# Auto.net
KiCad netlist of a schematic drawn in Altium Designer
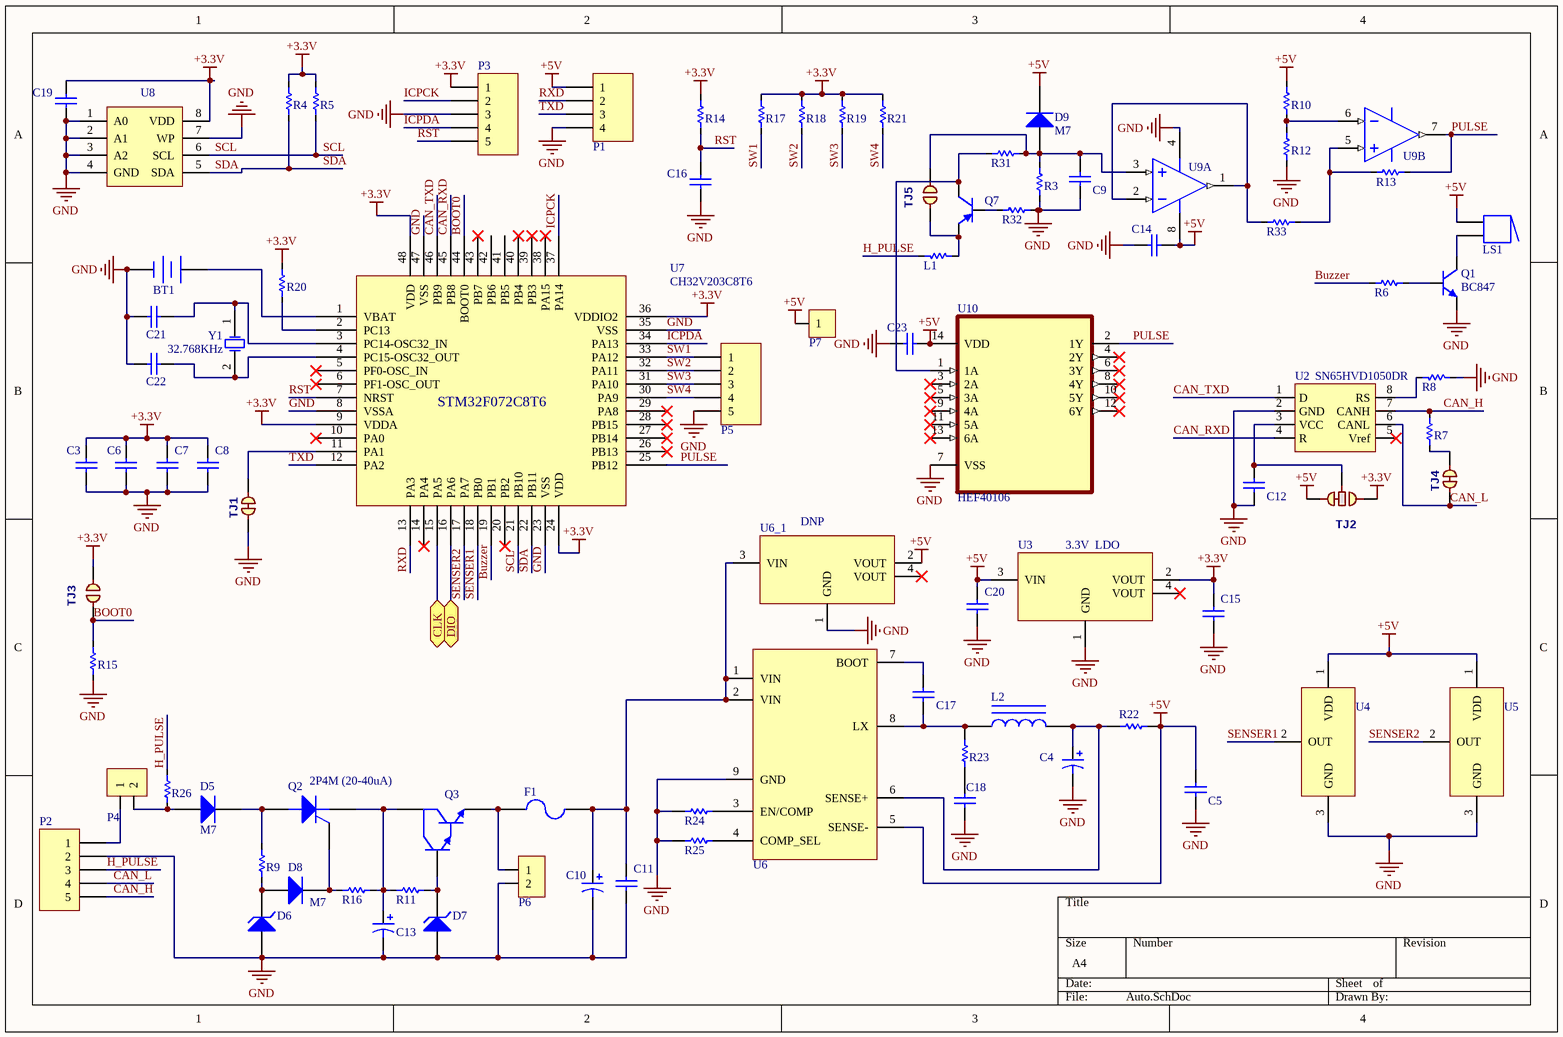
[diagram p0: Auto.SchDoc]

(export (version "E")
  (design (tool "Eeschema 10.0.6"))
  (components
    (comp (ref "BT1")
      (value "3V")
      (footprint "Battery Holder(CR2032)")
      (description "Cell Battery")
      (fields (field (name "MANUFACTURER PART NUMBER") "Standard"))
      (libsource (lib "Ravi") (part "Battery"))
    )
    (comp (ref "C3")
      (value "0.1uF/50V")
      (footprint "C0603")
      (description "CAP CER 0.1UF 50V X7R 0603")
      (fields (field (name "MANUFACTURER PART NUMBER") "0603B104K500CT"))
      (libsource (lib "Devices") (part "Capacitor_Ceramic"))
    )
    (comp (ref "C4")
      (value "220uF/16V")
      (footprint "C220uF25V")
      (description "220 µF 16 V Aluminum Electrolytic Capacitors Radial")
      (fields (field (name "MANUFACTURER PART NUMBER") "Standard"))
      (libsource (lib "Ravi") (part "Capacitor_Electrolytic"))
    )
    (comp (ref "C5")
      (value "0.1uF/50V")
      (footprint "C0603")
      (description "CAP CER 0.1UF 50V X7R 0603")
      (fields (field (name "MANUFACTURER PART NUMBER") "0603B104K500CT"))
      (libsource (lib "Ravi") (part "Capacitor_Ceramic"))
    )
    (comp (ref "C6")
      (value "0.1uF/50V")
      (footprint "C0603")
      (description "CAP CER 0.1UF 50V X7R 0603")
      (fields (field (name "MANUFACTURER PART NUMBER") "0603B104K500CT"))
      (libsource (lib "Devices") (part "Capacitor_Ceramic"))
    )
    (comp (ref "C7")
      (value "0.1uF/50V")
      (footprint "C0603")
      (description "CAP CER 0.1UF 50V X7R 0603")
      (fields (field (name "MANUFACTURER PART NUMBER") "0603B104K500CT"))
      (libsource (lib "Devices") (part "Capacitor_Ceramic"))
    )
    (comp (ref "C8")
      (value "0.1uF/50V")
      (footprint "C0603")
      (description "CAP CER 0.1UF 50V X7R 0603")
      (fields (field (name "MANUFACTURER PART NUMBER") "0603B104K500CT"))
      (libsource (lib "Devices") (part "Capacitor_Ceramic"))
    )
    (comp (ref "C9")
      (value "0.1uF/50V")
      (footprint "C0603")
      (description "CAP CER 0.1UF 50V X7R 0603")
      (fields (field (name "MANUFACTURER PART NUMBER") "0603B104K500CT"))
      (libsource (lib "Ravi") (part "Capacitor_Ceramic"))
    )
    (comp (ref "C10")
      (value "1000uF/25V")
      (footprint "C1000uF25V")
      (description "CAP ALUM 1000UF 20% 25V RADIAL")
      (fields (field (name "MANUFACTURER PART NUMBER") "Standard"))
      (libsource (lib "Ravi") (part "Capacitor_Electrolytic"))
    )
    (comp (ref "C11")
      (value "0.1uF/50V")
      (footprint "C0805")
      (description "CAP CER 0.1UF 50V X7R 0603")
      (fields (field (name "MANUFACTURER PART NUMBER") "0603B104K500CT"))
      (libsource (lib "Devices") (part "Capacitor_Ceramic"))
    )
    (comp (ref "C12")
      (value "0.1uF/50V")
      (footprint "C0603")
      (description "CAP CER 0.1UF 50V X7R 0603")
      (fields (field (name "MANUFACTURER PART NUMBER") "0603B104K500CT"))
      (libsource (lib "Devices") (part "Capacitor_Ceramic"))
    )
    (comp (ref "C13")
      (value "1000uF/50V")
      (footprint "C1000uF50V")
      (description "CAP ALUM 1000UF 20% 35V RADIAL")
      (fields (field (name "MANUFACTURER PART NUMBER") "Standard"))
      (libsource (lib "Ravi") (part "Capacitor_Electrolytic"))
    )
    (comp (ref "C14")
      (value "0.1uF/50V")
      (footprint "C0603")
      (description "CAP CER 0.1UF 50V X7R 0603")
      (fields (field (name "MANUFACTURER PART NUMBER") "0603B104K500CT"))
      (libsource (lib "Ravi") (part "Capacitor_Ceramic"))
    )
    (comp (ref "C15")
      (value "10uF")
      (footprint "C0603")
      (description "CAP CER 10UF 10V X5R 0603")
      (fields (field (name "MANUFACTURER PART NUMBER") "CL10A106MP8NNNC"))
      (libsource (lib "Devices") (part "Capacitor_Ceramic"))
    )
    (comp (ref "C16")
      (value "DNP")
      (footprint "C0603")
      (libsource (lib "Devices") (part "Capacitor_Ceramic"))
    )
    (comp (ref "C17")
      (value "0.1uF/50V")
      (footprint "C0603")
      (description "CAP CER 0.1UF 50V X7R 0603")
      (fields (field (name "MANUFACTURER PART NUMBER") "0603B104K500CT"))
      (libsource (lib "Ravi") (part "Capacitor_Ceramic"))
    )
    (comp (ref "C18")
      (value "3.3nF")
      (footprint "C0603")
      (description "CAP CER 3300PF 50V X7R 0603")
      (fields (field (name "MANUFACTURER PART NUMBER") "CC0603KRX7R9BB332"))
      (libsource (lib "Ravi") (part "Capacitor_Ceramic"))
    )
    (comp (ref "C19")
      (value "0.1uF/50V")
      (footprint "C0603")
      (description "CAP CER 0.1UF 50V X7R 0603")
      (fields (field (name "MANUFACTURER PART NUMBER") "0603B104K500CT"))
      (libsource (lib "Devices") (part "Capacitor_Ceramic"))
    )
    (comp (ref "C20")
      (value "10uF")
      (footprint "C0603")
      (description "CAP CER 10UF 10V X5R 0603")
      (fields (field (name "MANUFACTURER PART NUMBER") "CL10A106MP8NNNC"))
      (libsource (lib "Devices") (part "Capacitor_Ceramic"))
    )
    (comp (ref "C21")
      (value "22pF/50V")
      (footprint "C0603")
      (description "CAP CER 22PF 50V C0G/NPO 0603")
      (fields (field (name "MANUFACTURER PART NUMBER") "CC0603JRNPO9BN220"))
      (libsource (lib "Devices") (part "Capacitor_Ceramic"))
    )
    (comp (ref "C22")
      (value "22pF/50V")
      (footprint "C0603")
      (description "CAP CER 22PF 50V C0G/NPO 0603")
      (fields (field (name "MANUFACTURER PART NUMBER") "CC0603JRNPO9BN220"))
      (libsource (lib "Devices") (part "Capacitor_Ceramic"))
    )
    (comp (ref "C23")
      (value "0.1uF/50V")
      (footprint "C0603")
      (description "CAP CER 0.1UF 50V X7R 0603")
      (fields (field (name "MANUFACTURER PART NUMBER") "0603B104K500CT"))
      (libsource (lib "Ravi") (part "Capacitor_Ceramic"))
    )
    (comp (ref "D5")
      (value "M7")
      (footprint "DO-241")
      (description "General Purpose Diode")
      (libsource (lib "Ravi") (part "Diode"))
    )
    (comp (ref "D6")
      (value "12V/1W")
      (footprint "LL-41")
      (description "Zener Diode")
      (fields (field (name "MANUFACTURER PART NUMBER") "SML4742A-E3/61"))
      (libsource (lib "Ravi") (part "D Zener"))
    )
    (comp (ref "D7")
      (value "12V/1W")
      (footprint "LL-41")
      (description "Zener Diode")
      (fields (field (name "MANUFACTURER PART NUMBER") "SML4742A-E3/61"))
      (libsource (lib "Ravi") (part "D Zener"))
    )
    (comp (ref "D8")
      (value "M7")
      (footprint "DO-241")
      (description "General Purpose Diode")
      (libsource (lib "Ravi") (part "Diode"))
    )
    (comp (ref "D9")
      (value "M7")
      (footprint "SMA")
      (description "General Purpose Diode")
      (libsource (lib "Ravi") (part "Diode"))
    )
    (comp (ref "F1")
      (value "750mA PTC")
      (footprint "1812(PTC Fuse)")
      (description "PTC RESET FUSE 24V 750MA 1812")
      (fields (field (name "MANUFACTURER PART NUMBER") "WT-1812-075"))
      (libsource (lib "Devices") (part "Fuse"))
    )
    (comp (ref "L1")
      (value "Ferrite Bead")
      (footprint "R0603")
      (description "Ferrite Bead  200mΩ ±25% 60Ω@100MHz")
      (fields (field (name "MANUFACTURER PART NUMBER") "FCM1608KF-600T07"))
      (libsource (lib "Devices") (part "Res1"))
    )
    (comp (ref "L2")
      (value "22uH/1.8A")
      (footprint "Ferrite_Coil_22uH")
      (description "FIXED IND 22UH 1.8A 116MOHM SMD")
      (fields (field (name "MANUFACTURER PART NUMBER") "SWPA6045S220MT"))
      (libsource (lib "Devices") (part "Ferrite_Coil"))
    )
    (comp (ref "LS1")
      (value "Buzzer")
      (footprint "Buzzer")
      (description "Magnetic Transducer Buzzer")
      (fields (field (name "MANUFACTURER PART NUMBER") "Standard"))
      (libsource (lib "Ravi") (part "Buzzer"))
    )
    (comp (ref "P1")
      (value "2515-4")
      (footprint "HDR1X4")
      (description "Header, 4-Pin")
      (fields (field (name "MANUFACTURER PART NUMBER") "Standard"))
      (libsource (lib "Ravi") (part "Header 4"))
    )
    (comp (ref "P2")
      (value "Wire Harness")
      (footprint "Connector_508_5pin")
      (description "Header, 5-Pin")
      (fields (field (name "MANUFACTURER PART NUMBER") "Custom"))
      (libsource (lib "Connector") (part "Header 5"))
    )
    (comp (ref "P3")
      (value "5 Pin Header")
      (footprint "HDR1X5")
      (description "Header, 5-Pin")
      (fields (field (name "MANUFACTURER PART NUMBER") "Standard"))
      (libsource (lib "Ravi") (part "Header 5"))
    )
    (comp (ref "P4")
      (value "2515-2")
      (footprint "HDR1X2_2515")
      (fields (field (name "MANUFACTURER PART NUMBER") "Standard"))
      (libsource (lib "") (part "Header 2X1_1"))
    )
    (comp (ref "P5")
      (value "2515-5")
      (footprint "HDR1X5_2515")
      (description "Header, 5-Pin")
      (fields (field (name "MANUFACTURER PART NUMBER") "DNP"))
      (libsource (lib "Ravi") (part "Header 5"))
    )
    (comp (ref "P6")
      (value "2515-2")
      (footprint "HDR1X2_2515")
      (fields (field (name "MANUFACTURER PART NUMBER") "DNP"))
      (libsource (lib "Connector") (part "Header 2X1"))
    )
    (comp (ref "P7") (value "Header 1X1") (footprint "HDR1X1") (libsource (lib "Ravi") (part "Header 1X1")))
    (comp (ref "Q1")
      (value "BC847")
      (footprint "SOT-23")
      (description "TRANS NPN 45V 0.1A SOT-23-3")
      (libsource (lib "Ravi") (part "NPN"))
    )
    (comp (ref "Q2")
      (value "2P4M (20-40uA)")
      (footprint "DPAK_SOT423_252")
      (description "THYRISTOR, P-GATE,  2A,  400V")
      (fields (field (name "MANUFACTURER PART NUMBER") "2P4M"))
      (libsource (lib "Devices") (part "SCR"))
    )
    (comp (ref "Q3")
      (value "MJD122")
      (footprint "DPAK_SOT423_252")
      (description "TRANS NPN DARL 100V 8A TO-252-2L")
      (libsource (lib "Devices") (part "NPN1"))
    )
    (comp (ref "Q7")
      (value "BC857")
      (footprint "SOT-23")
      (description "TRANS PNP 45V 0.1A SOT23-3")
      (libsource (lib "Ravi") (part "PNP"))
    )
    (comp (ref "R3")
      (value "10K")
      (footprint "R0603")
      (description "RES 10K OHM 1% 1/10W 0603")
      (fields (field (name "MANUFACTURER PART NUMBER") "CR16-1002-FL"))
      (libsource (lib "Ravi") (part "Res1"))
    )
    (comp (ref "R4")
      (value "4.7K")
      (footprint "R0603")
      (description "RES 4.7K OHM 1% 1/10W 0603")
      (fields (field (name "MANUFACTURER PART NUMBER") "CR16-4701-FL"))
      (libsource (lib "Devices") (part "Res1"))
    )
    (comp (ref "R5")
      (value "4.7K")
      (footprint "R0603")
      (description "RES 4.7K OHM 1% 1/10W 0603")
      (fields (field (name "MANUFACTURER PART NUMBER") "CR16-4701-FL"))
      (libsource (lib "Devices") (part "Res1"))
    )
    (comp (ref "R6")
      (value "4.7K")
      (footprint "R0603")
      (description "RES 4.7K OHM 1% 1/10W 0603")
      (fields (field (name "MANUFACTURER PART NUMBER") "CR16-4701-FL"))
      (libsource (lib "Devices") (part "Res1"))
    )
    (comp (ref "R7")
      (value "120R")
      (footprint "R0603")
      (description "RES 120 OHM 1% 1/10W 0603")
      (fields (field (name "MANUFACTURER PART NUMBER") "RC0603FR-07120RL"))
      (libsource (lib "Devices") (part "Res1"))
    )
    (comp (ref "R8")
      (value "0R")
      (footprint "R0603")
      (description "RES 0 OHM 1% 1/10W 0603")
      (fields (field (name "MANUFACTURER PART NUMBER") "RC0603FR-070RL"))
      (libsource (lib "Devices") (part "Res1"))
    )
    (comp (ref "R9")
      (value "1K")
      (footprint "R1206")
      (description "Resistor")
      (fields (field (name "MANUFACTURER PART NUMBER") "RC1206JR-071KL"))
      (libsource (lib "Devices") (part "Res1"))
    )
    (comp (ref "R10")
      (value "10K")
      (footprint "R0603")
      (description "RES 10K OHM 1% 1/10W 0603")
      (fields (field (name "MANUFACTURER PART NUMBER") "CR16-1002-FL"))
      (libsource (lib "Ravi") (part "Res1"))
    )
    (comp (ref "R11")
      (value "2.2K")
      (footprint "R1206")
      (description "RES 2.2K OHM 1% 1/4W 1206")
      (fields (field (name "MANUFACTURER PART NUMBER") "CR32-2201-FL"))
      (libsource (lib "Devices") (part "Res1"))
    )
    (comp (ref "R12")
      (value "2.2K")
      (footprint "R0603")
      (description "RES 2.2K OHM 1% 1/10W 0603")
      (fields (field (name "MANUFACTURER PART NUMBER") "RC0603JR-072K2L"))
      (libsource (lib "Ravi") (part "Res1"))
    )
    (comp (ref "R13")
      (value "100K")
      (footprint "R0603")
      (description "RES 100K OHM 1% 1/4W 0603")
      (fields (field (name "MANUFACTURER PART NUMBER") "CR-03JTP-100KR"))
      (libsource (lib "Ravi") (part "Res1"))
    )
    (comp (ref "R14")
      (value "DNP")
      (footprint "R0603")
      (description "Resistor")
      (libsource (lib "Ravi") (part "Res1"))
    )
    (comp (ref "R15")
      (value "10K")
      (footprint "R0603")
      (description "RES 10K OHM 1% 1/10W 0603")
      (fields (field (name "MANUFACTURER PART NUMBER") "CR16-1002-FL"))
      (libsource (lib "Devices") (part "Res1"))
    )
    (comp (ref "R16")
      (value "2.2K")
      (footprint "R1206")
      (description "RES 2.2K OHM 1% 1/4W 1206")
      (fields (field (name "MANUFACTURER PART NUMBER") "CR32-2201-FL"))
      (libsource (lib "Devices") (part "Res1"))
    )
    (comp (ref "R17")
      (value "DNP")
      (footprint "R0603")
      (description "Resistor")
      (libsource (lib "Ravi") (part "Res1"))
    )
    (comp (ref "R18")
      (value "DNP")
      (footprint "R0603")
      (description "Resistor")
      (libsource (lib "Ravi") (part "Res1"))
    )
    (comp (ref "R19")
      (value "DNP")
      (footprint "R0603")
      (description "Resistor")
      (libsource (lib "Ravi") (part "Res1"))
    )
    (comp (ref "R20")
      (value "10K")
      (footprint "R0603")
      (description "RES 10K OHM 1% 1/10W 0603")
      (fields (field (name "MANUFACTURER PART NUMBER") "CR16-1002-FL"))
      (libsource (lib "Ravi") (part "Res1"))
    )
    (comp (ref "R21")
      (value "DNP")
      (footprint "R0603")
      (description "Resistor")
      (libsource (lib "Ravi") (part "Res1"))
    )
    (comp (ref "R22")
      (value "0.062R")
      (footprint "R1210")
      (description "RES 0.062 OHM 2/3W 1% 1210")
      (fields (field (name "MANUFACTURER PART NUMBER") "RL2110FR-070R062L"))
      (libsource (lib "") (part "Res1_1"))
    )
    (comp (ref "R23")
      (value "3R3")
      (footprint "R0603")
      (description "RES 3.3 OHM 1% 1/10W 0603")
      (fields (field (name "MANUFACTURER PART NUMBER") "RC0603FR-073R3L"))
      (libsource (lib "") (part "Res1_1"))
    )
    (comp (ref "R24")
      (value "DNP")
      (footprint "R0603")
      (description "Resistor")
      (libsource (lib "") (part "Res1_1"))
    )
    (comp (ref "R25")
      (value "DNP")
      (footprint "R0603")
      (description "Resistor")
      (libsource (lib "") (part "Res1_1"))
    )
    (comp (ref "R26")
      (value "1K")
      (footprint "R1206")
      (description "Resistor")
      (fields (field (name "MANUFACTURER PART NUMBER") "RC1206JR-071KL"))
      (libsource (lib "Devices") (part "Res1"))
    )
    (comp (ref "R31")
      (value "4.7K")
      (footprint "R0603")
      (description "RES 4.7K OHM 1% 1/10W 0603")
      (fields (field (name "MANUFACTURER PART NUMBER") "CR16-4701-FL"))
      (libsource (lib "Ravi") (part "Res1"))
    )
    (comp (ref "R32")
      (value "10K")
      (footprint "R0603")
      (description "RES 10K OHM 1% 1/10W 0603")
      (fields (field (name "MANUFACTURER PART NUMBER") "CR16-1002-FL"))
      (libsource (lib "Ravi") (part "Res1"))
    )
    (comp (ref "R33")
      (value "2.2K")
      (footprint "R0603")
      (description "RES 2.2K OHM 1% 1/10W 0603")
      (fields (field (name "MANUFACTURER PART NUMBER") "RC0603JR-072K2L"))
      (libsource (lib "Ravi") (part "Res1"))
    )
    (comp (ref "TJ1")
      (value "~")
      (footprint "PAD_JUMPER_2_NC")
      (libsource (lib "Ravi") (part "JUMPER-PAD-2-NC_BY_TRACE"))
    )
    (comp (ref "TJ2")
      (value "~")
      (footprint "PAD_JUMPER_3_12NC")
      (libsource (lib "Ravi") (part "JUMPER-PAD-3-1OF2_NC_BY_TRACE_SMALL"))
    )
    (comp (ref "TJ3")
      (value "~")
      (footprint "PAD_JUMPER_2_NO")
      (libsource (lib "Ravi") (part "JUMPER-PAD-2-NO_BY_TRACE"))
    )
    (comp (ref "TJ4")
      (value "~")
      (footprint "PAD_JUMPER_2_NC")
      (libsource (lib "Ravi") (part "JUMPER-PAD-2-NC_BY_TRACE"))
    )
    (comp (ref "TJ5")
      (value "JUMPER-PAD-2-NO_BY_TRACE")
      (footprint "PAD_JUMPER_2_NO")
      (libsource (lib "Ravi") (part "JUMPER-PAD-2-NO_BY_TRACE"))
    )
    (comp (ref "U2")
      (value "SN65HVD1050DR")
      (footprint "SOIC-8N")
      (description "IC TRANSCEIVER HALF 1/1 8SOIC")
      (libsource (lib "Ravi") (part "SN65HVD230"))
    )
    (comp (ref "U3")
      (value "3.3V  LDO")
      (footprint "SOT223")
      (description "IC REG LINEAR 3.3V 1A SOT-223")
      (fields (field (name "MANUFACTURER PART NUMBER") "LD1117AG-33-AA3-A-R"))
      (libsource (lib "Ravi") (part "LM1117"))
    )
    (comp (ref "U4")
      (value "UHE4913G")
      (footprint "SOT-23 - Sensor")
      (description "Digital Switch Omnipolar Hall Effect SOT-23")
      (fields (field (name "MANUFACTURER PART NUMBER") "UHE4913G-AE3-R"))
      (libsource (lib "Devices") (part "AH1802"))
    )
    (comp (ref "U5")
      (value "UHE4913G")
      (footprint "SOT-23 - Sensor")
      (description "Digital Switch Omnipolar Hall Effect SOT-23")
      (fields (field (name "MANUFACTURER PART NUMBER") "UHE4913G-AE3-R"))
      (libsource (lib "Devices") (part "AH1802"))
    )
    (comp (ref "U6")
      (value "uP9602SW8")
      (footprint "SO PowerPAD")
      (description "DC-to-DC Converter Control Circuit")
      (libsource (lib "Ravi") (part "uP9601T"))
    )
    (comp (ref "U6_1") (value "DNP") (footprint "SOT223") (libsource (lib "Ravi") (part "LM1117")))
    (comp (ref "U7")
      (value "CH32V203C8T6")
      (footprint "TQFP48")
      (description "64K Flash value RISC MCU.  12-bit ADC, DMA, TIM, USART, I2C, SPI, and so on.")
      (libsource (lib "Ravi") (part "STM32F072C8T6"))
    )
    (comp (ref "U8")
      (value "24C02")
      (footprint "SOIC-8N")
      (description "IC EEPROM 2KBIT I2C 400KHZ 8SOIC")
      (fields (field (name "MANUFACTURER PART NUMBER") "FT24C02A-KSR-T"))
      (libsource (lib "Ravi") (part "24Cxx"))
    )
    (comp (ref "U9")
      (value "LM358")
      (footprint "SOIC-8N")
      (description "IC OPAMP GP 2 CIRCUIT 8SOIC")
      (fields (field (name "MANUFACTURER PART NUMBER") "LM358DT"))
      (libsource (lib "Ravi") (part "LM158"))
    )
    (comp (ref "U10")
      (value "HEF40106")
      (footprint "SOIC127P600X175-14N")
      (description "IC INVERT SCHMITT 6CH 1-INP 14SO")
      (fields (field (name "MANUFACTURER PART NUMBER") "HEF40106BT"))
      (libsource (lib "Ravi") (part "HEF40106BT"))
    )
    (comp (ref "Y1")
      (value "32.768KHz")
      (footprint "Craystal_Radial_2x6")
      (description "Crystal 32.768kHz ±10ppm 12.5pF 40kΩ DT-26")
      (fields (field (name "MANUFACTURER PART NUMBER") "TAXD32768K2BGBBZT2S"))
      (libsource (lib "Devices") (part "XTAL"))
    )
  )
  (nets
    (net (code "1") (name "+3.3V") (class "Default")
      (node (ref "C15") (pin "2") (pinfunction "2_2") (pintype "passive"))
      (node (ref "C19") (pin "1") (pinfunction "1_1") (pintype "passive"))
      (node (ref "C3") (pin "2") (pinfunction "2_2") (pintype "passive"))
      (node (ref "C6") (pin "2") (pinfunction "2_2") (pintype "passive"))
      (node (ref "C7") (pin "2") (pinfunction "2_2") (pintype "passive"))
      (node (ref "C8") (pin "2") (pinfunction "2_2") (pintype "passive"))
      (node (ref "P3") (pin "1") (pinfunction "1_1") (pintype "passive"))
      (node (ref "R14") (pin "2") (pinfunction "2_2") (pintype "passive"))
      (node (ref "R17") (pin "2") (pinfunction "2_2") (pintype "passive"))
      (node (ref "R18") (pin "2") (pinfunction "2_2") (pintype "passive"))
      (node (ref "R19") (pin "2") (pinfunction "2_2") (pintype "passive"))
      (node (ref "R20") (pin "2") (pinfunction "2_2") (pintype "passive"))
      (node (ref "R21") (pin "2") (pinfunction "2_2") (pintype "passive"))
      (node (ref "R4") (pin "2") (pinfunction "2_2") (pintype "passive"))
      (node (ref "R5") (pin "2") (pinfunction "2_2") (pintype "passive"))
      (node (ref "TJ2") (pin "3") (pinfunction "3_3") (pintype "passive"))
      (node (ref "TJ3") (pin "2") (pinfunction "2_2") (pintype "passive"))
      (node (ref "U3") (pin "2") (pinfunction "VOUT_2") (pintype "passive"))
      (node (ref "U7") (pin "24") (pinfunction "VDD_24") (pintype "passive"))
      (node (ref "U7") (pin "36") (pinfunction "VDDIO2_36") (pintype "power_in"))
      (node (ref "U7") (pin "48") (pinfunction "VDD_48") (pintype "passive"))
      (node (ref "U7") (pin "9") (pinfunction "VDDA_9") (pintype "passive"))
      (node (ref "U8") (pin "8") (pinfunction "VDD_8") (pintype "power_in"))
    )
    (net (code "2") (name "+5V") (class "Default")
      (node (ref "C14") (pin "2") (pinfunction "2_2") (pintype "passive"))
      (node (ref "C20") (pin "2") (pinfunction "2_2") (pintype "passive"))
      (node (ref "C23") (pin "2") (pinfunction "2_2") (pintype "passive"))
      (node (ref "C5") (pin "2") (pinfunction "2_2") (pintype "passive"))
      (node (ref "D9") (pin "2") (pinfunction "K_2") (pintype "passive"))
      (node (ref "LS1") (pin "1") (pinfunction "1_1") (pintype "passive"))
      (node (ref "P1") (pin "1") (pinfunction "1_1") (pintype "passive"))
      (node (ref "P7") (pin "1") (pinfunction "1_1") (pintype "passive"))
      (node (ref "R10") (pin "2") (pinfunction "2_2") (pintype "passive"))
      (node (ref "R22") (pin "2") (pinfunction "2_2") (pintype "passive"))
      (node (ref "TJ2") (pin "1") (pinfunction "1_1") (pintype "passive"))
      (node (ref "U10") (pin "14") (pinfunction "VDD_14") (pintype "power_in"))
      (node (ref "U3") (pin "3") (pinfunction "VIN_3") (pintype "passive"))
      (node (ref "U4") (pin "1") (pinfunction "VDD_1") (pintype "passive"))
      (node (ref "U5") (pin "1") (pinfunction "VDD_1") (pintype "passive"))
      (node (ref "U6") (pin "5") (pinfunction "SENSE-_5") (pintype "passive"))
      (node (ref "U6_1") (pin "2") (pinfunction "VOUT_2") (pintype "passive"))
      (node (ref "U9") (pin "8") (pinfunction "VCC_8") (pintype "power_in"))
    )
    (net (code "3") (name "/BOOT0") (class "Default")
      (node (ref "R15") (pin "1") (pinfunction "1_1") (pintype "passive"))
      (node (ref "TJ3") (pin "1") (pinfunction "1_1") (pintype "passive"))
      (node (ref "U7") (pin "44") (pinfunction "BOOT0_44") (pintype "passive"))
    )
    (net (code "4") (name "/Buzzer") (class "Default")
      (node (ref "R6") (pin "2") (pinfunction "2_2") (pintype "passive"))
      (node (ref "U7") (pin "19") (pinfunction "PB1_19") (pintype "power_in"))
    )
    (net (code "5") (name "/CAN_H") (class "Default")
      (node (ref "P2") (pin "5") (pinfunction "5_5") (pintype "passive"))
      (node (ref "R7") (pin "2") (pinfunction "2_2") (pintype "passive"))
      (node (ref "U2") (pin "7") (pinfunction "CANH_7") (pintype "passive"))
    )
    (net (code "6") (name "/CAN_L") (class "Default")
      (node (ref "P2") (pin "4") (pinfunction "4_4") (pintype "passive"))
      (node (ref "TJ4") (pin "1") (pinfunction "1_1") (pintype "passive"))
      (node (ref "U2") (pin "6") (pinfunction "CANL_6") (pintype "passive"))
    )
    (net (code "7") (name "/CAN_RXD") (class "Default")
      (node (ref "U2") (pin "4") (pinfunction "R_4") (pintype "power_in"))
      (node (ref "U7") (pin "45") (pinfunction "PB8_45") (pintype "passive"))
    )
    (net (code "8") (name "/CAN_TXD") (class "Default")
      (node (ref "U2") (pin "1") (pinfunction "D_1") (pintype "passive"))
      (node (ref "U7") (pin "46") (pinfunction "PB9_46") (pintype "passive"))
    )
    (net (code "9") (name "/CLK") (class "Default")
      (node (ref "U7") (pin "15") (pinfunction "PA5_15") (pintype "passive"))
    )
    (net (code "10") (name "/DIO") (class "Default")
      (node (ref "U7") (pin "16") (pinfunction "PA6_16") (pintype "passive"))
    )
    (net (code "11") (name "/H_PULSE") (class "Default")
      (node (ref "L1") (pin "1") (pinfunction "1_1") (pintype "passive"))
      (node (ref "P2") (pin "3") (pinfunction "3_3") (pintype "passive"))
      (node (ref "R26") (pin "2") (pinfunction "2_2") (pintype "passive"))
    )
    (net (code "12") (name "/ICPCK") (class "Default")
      (node (ref "P3") (pin "2") (pinfunction "2_2") (pintype "passive"))
      (node (ref "U7") (pin "37") (pinfunction "PA14_37") (pintype "passive"))
    )
    (net (code "13") (name "/ICPDA") (class "Default")
      (node (ref "P3") (pin "4") (pinfunction "4_4") (pintype "passive"))
      (node (ref "U7") (pin "34") (pinfunction "PA13_34") (pintype "power_in"))
    )
    (net (code "14") (name "/PULSE") (class "Default")
      (node (ref "R13") (pin "1") (pinfunction "1_1") (pintype "passive"))
      (node (ref "U10") (pin "2") (pinfunction "1Y_2") (pintype "passive"))
      (node (ref "U7") (pin "25") (pinfunction "PB12_25") (pintype "passive"))
      (node (ref "U9") (pin "7") (pinfunction "OUT_7") (pintype "output"))
    )
    (net (code "15") (name "/RST") (class "Default")
      (node (ref "C16") (pin "1") (pinfunction "1_1") (pintype "passive"))
      (node (ref "P3") (pin "5") (pinfunction "5_5") (pintype "passive"))
      (node (ref "R14") (pin "1") (pinfunction "1_1") (pintype "passive"))
      (node (ref "U7") (pin "7") (pinfunction "NRST_7") (pintype "passive"))
    )
    (net (code "16") (name "/RXD") (class "Default")
      (node (ref "P1") (pin "2") (pinfunction "2_2") (pintype "passive"))
      (node (ref "U7") (pin "13") (pinfunction "PA3_13") (pintype "passive"))
    )
    (net (code "17") (name "/SCL") (class "Default")
      (node (ref "R5") (pin "1") (pinfunction "1_1") (pintype "passive"))
      (node (ref "U7") (pin "21") (pinfunction "PB10_21") (pintype "passive"))
      (node (ref "U8") (pin "6") (pinfunction "SCL_6") (pintype "passive"))
    )
    (net (code "18") (name "/SDA") (class "Default")
      (node (ref "R4") (pin "1") (pinfunction "1_1") (pintype "passive"))
      (node (ref "U7") (pin "22") (pinfunction "PB11_22") (pintype "passive"))
      (node (ref "U8") (pin "5") (pinfunction "SDA_5") (pintype "passive"))
    )
    (net (code "19") (name "/SENSER1") (class "Default")
      (node (ref "U4") (pin "2") (pinfunction "OUT_2") (pintype "passive"))
      (node (ref "U7") (pin "18") (pinfunction "PB0_18") (pintype "passive"))
    )
    (net (code "20") (name "/SENSER2") (class "Default")
      (node (ref "U5") (pin "2") (pinfunction "OUT_2") (pintype "passive"))
      (node (ref "U7") (pin "17") (pinfunction "PA7_17") (pintype "passive"))
    )
    (net (code "21") (name "/SW1") (class "Default")
      (node (ref "P5") (pin "1") (pinfunction "1_1") (pintype "passive"))
      (node (ref "R17") (pin "1") (pinfunction "1_1") (pintype "passive"))
      (node (ref "U7") (pin "33") (pinfunction "PA12_33") (pintype "power_in"))
    )
    (net (code "22") (name "/SW2") (class "Default")
      (node (ref "P5") (pin "2") (pinfunction "2_2") (pintype "passive"))
      (node (ref "R18") (pin "1") (pinfunction "1_1") (pintype "passive"))
      (node (ref "U7") (pin "32") (pinfunction "PA11_32") (pintype "passive"))
    )
    (net (code "23") (name "/SW3") (class "Default")
      (node (ref "P5") (pin "3") (pinfunction "3_3") (pintype "passive"))
      (node (ref "R19") (pin "1") (pinfunction "1_1") (pintype "passive"))
      (node (ref "U7") (pin "31") (pinfunction "PA10_31") (pintype "passive"))
    )
    (net (code "24") (name "/SW4") (class "Default")
      (node (ref "P5") (pin "4") (pinfunction "4_4") (pintype "passive"))
      (node (ref "R21") (pin "1") (pinfunction "1_1") (pintype "passive"))
      (node (ref "U7") (pin "30") (pinfunction "PA9_30") (pintype "passive"))
    )
    (net (code "25") (name "/TXD") (class "Default")
      (node (ref "P1") (pin "3") (pinfunction "3_3") (pintype "passive"))
      (node (ref "U7") (pin "12") (pinfunction "PA2_12") (pintype "passive"))
    )
    (net (code "26") (name "GND") (class "Default")
      (node (ref "BT1") (pin "2") (pinfunction "-_2") (pintype "passive"))
      (node (ref "C10") (pin "2") (pinfunction "2_2") (pintype "passive"))
      (node (ref "C11") (pin "1") (pinfunction "1_1") (pintype "passive"))
      (node (ref "C12") (pin "1") (pinfunction "1_1") (pintype "passive"))
      (node (ref "C13") (pin "2") (pinfunction "2_2") (pintype "passive"))
      (node (ref "C14") (pin "1") (pinfunction "1_1") (pintype "passive"))
      (node (ref "C15") (pin "1") (pinfunction "1_1") (pintype "passive"))
      (node (ref "C16") (pin "2") (pinfunction "2_2") (pintype "passive"))
      (node (ref "C18") (pin "1") (pinfunction "1_1") (pintype "passive"))
      (node (ref "C19") (pin "2") (pinfunction "2_2") (pintype "passive"))
      (node (ref "C20") (pin "1") (pinfunction "1_1") (pintype "passive"))
      (node (ref "C21") (pin "2") (pinfunction "2_2") (pintype "passive"))
      (node (ref "C22") (pin "2") (pinfunction "2_2") (pintype "passive"))
      (node (ref "C23") (pin "1") (pinfunction "1_1") (pintype "passive"))
      (node (ref "C3") (pin "1") (pinfunction "1_1") (pintype "passive"))
      (node (ref "C4") (pin "2") (pinfunction "2_2") (pintype "passive"))
      (node (ref "C5") (pin "1") (pinfunction "1_1") (pintype "passive"))
      (node (ref "C6") (pin "1") (pinfunction "1_1") (pintype "passive"))
      (node (ref "C7") (pin "1") (pinfunction "1_1") (pintype "passive"))
      (node (ref "C8") (pin "1") (pinfunction "1_1") (pintype "passive"))
      (node (ref "C9") (pin "2") (pinfunction "2_2") (pintype "passive"))
      (node (ref "D6") (pin "1") (pinfunction "A_1") (pintype "passive"))
      (node (ref "D7") (pin "1") (pinfunction "A_1") (pintype "passive"))
      (node (ref "P1") (pin "4") (pinfunction "4_4") (pintype "passive"))
      (node (ref "P2") (pin "2") (pinfunction "2_2") (pintype "passive"))
      (node (ref "P3") (pin "3") (pinfunction "3_3") (pintype "passive"))
      (node (ref "P5") (pin "5") (pinfunction "5_5") (pintype "passive"))
      (node (ref "P6") (pin "2") (pinfunction "2_2") (pintype "passive"))
      (node (ref "Q1") (pin "2") (pinfunction "E_2") (pintype "passive"))
      (node (ref "R12") (pin "2") (pinfunction "2_2") (pintype "passive"))
      (node (ref "R15") (pin "2") (pinfunction "2_2") (pintype "passive"))
      (node (ref "R24") (pin "1") (pinfunction "1_1") (pintype "passive"))
      (node (ref "R25") (pin "1") (pinfunction "1_1") (pintype "passive"))
      (node (ref "R3") (pin "2") (pinfunction "2_2") (pintype "passive"))
      (node (ref "R32") (pin "1") (pinfunction "1_1") (pintype "passive"))
      (node (ref "R8") (pin "2") (pinfunction "2_2") (pintype "passive"))
      (node (ref "TJ1") (pin "1") (pinfunction "1_1") (pintype "passive"))
      (node (ref "U10") (pin "7") (pinfunction "VSS_7") (pintype "passive"))
      (node (ref "U2") (pin "2") (pinfunction "GND_2") (pintype "passive"))
      (node (ref "U3") (pin "1") (pinfunction "GND_1") (pintype "passive"))
      (node (ref "U4") (pin "3") (pinfunction "GND_3") (pintype "passive"))
      (node (ref "U5") (pin "3") (pinfunction "GND_3") (pintype "passive"))
      (node (ref "U6") (pin "9") (pinfunction "GND_9") (pintype "power_in"))
      (node (ref "U6_1") (pin "1") (pinfunction "GND_1") (pintype "passive"))
      (node (ref "U7") (pin "23") (pinfunction "VSS_23") (pintype "passive"))
      (node (ref "U7") (pin "35") (pinfunction "VSS_35") (pintype "power_in"))
      (node (ref "U7") (pin "47") (pinfunction "VSS_47") (pintype "passive"))
      (node (ref "U7") (pin "8") (pinfunction "VSSA_8") (pintype "passive"))
      (node (ref "U8") (pin "1") (pinfunction "A0_1") (pintype "passive"))
      (node (ref "U8") (pin "2") (pinfunction "A1_2") (pintype "passive"))
      (node (ref "U8") (pin "3") (pinfunction "A2_3") (pintype "passive"))
      (node (ref "U8") (pin "4") (pinfunction "GND_4") (pintype "power_in"))
      (node (ref "U8") (pin "7") (pinfunction "WP_7") (pintype "passive"))
      (node (ref "U9") (pin "4") (pinfunction "GND_4") (pintype "power_in"))
    )
    (net (code "27") (name "Net-(BT1-+)") (class "Default")
      (node (ref "BT1") (pin "1") (pinfunction "+_1") (pintype "passive"))
      (node (ref "U7") (pin "1") (pinfunction "VBAT_1") (pintype "power_in"))
    )
    (net (code "28") (name "Net-(C18-Pad2)") (class "Default")
      (node (ref "C18") (pin "2") (pinfunction "2_2") (pintype "passive"))
      (node (ref "R23") (pin "1") (pinfunction "1_1") (pintype "passive"))
    )
    (net (code "29") (name "Net-(D5-A)") (class "Default")
      (node (ref "D5") (pin "1") (pinfunction "A_1") (pintype "passive"))
      (node (ref "P4") (pin "2") (pinfunction "2_2") (pintype "passive"))
      (node (ref "R26") (pin "1") (pinfunction "1_1") (pintype "passive"))
    )
    (net (code "30") (name "Net-(D5-K)") (class "Default")
      (node (ref "D5") (pin "2") (pinfunction "K_2") (pintype "passive"))
      (node (ref "Q2") (pin "4") (pinfunction "A_4") (pintype "passive"))
      (node (ref "R9") (pin "2") (pinfunction "2_2") (pintype "passive"))
    )
    (net (code "31") (name "Net-(D6-K)") (class "Default")
      (node (ref "D6") (pin "2") (pinfunction "K_2") (pintype "passive"))
      (node (ref "D8") (pin "1") (pinfunction "A_1") (pintype "passive"))
      (node (ref "R9") (pin "1") (pinfunction "1_1") (pintype "passive"))
    )
    (net (code "32") (name "Net-(D7-K)") (class "Default")
      (node (ref "D7") (pin "2") (pinfunction "K_2") (pintype "passive"))
      (node (ref "Q3") (pin "1") (pinfunction "B_1") (pintype "passive"))
      (node (ref "R11") (pin "1") (pinfunction "1_1") (pintype "passive"))
    )
    (net (code "33") (name "Net-(D8-K)") (class "Default")
      (node (ref "D8") (pin "2") (pinfunction "K_2") (pintype "passive"))
      (node (ref "Q2") (pin "3") (pinfunction "G_3") (pintype "passive"))
      (node (ref "R16") (pin "2") (pinfunction "2_2") (pintype "passive"))
    )
    (net (code "34") (name "Net-(D9-A)") (class "Default")
      (node (ref "C9") (pin "1") (pinfunction "1_1") (pintype "passive"))
      (node (ref "D9") (pin "1") (pinfunction "A_1") (pintype "passive"))
      (node (ref "R3") (pin "1") (pinfunction "1_1") (pintype "passive"))
      (node (ref "R31") (pin "1") (pinfunction "1_1") (pintype "passive"))
      (node (ref "TJ5") (pin "2") (pinfunction "2_2") (pintype "passive"))
      (node (ref "U9") (pin "3") (pinfunction "IN+_3") (pintype "input"))
    )
    (net (code "35") (name "Net-(P2-Pad1)") (class "Default")
      (node (ref "P2") (pin "1") (pinfunction "1_1") (pintype "passive"))
      (node (ref "P4") (pin "1") (pinfunction "1_1") (pintype "passive"))
    )
    (net (code "36") (name "Net-(Q1-B)") (class "Default")
      (node (ref "Q1") (pin "1") (pinfunction "B_1") (pintype "passive"))
      (node (ref "R6") (pin "1") (pinfunction "1_1") (pintype "passive"))
    )
    (net (code "37") (name "Net-(Q1-C)") (class "Default")
      (node (ref "LS1") (pin "2") (pinfunction "2_2") (pintype "passive"))
      (node (ref "Q1") (pin "3") (pinfunction "C_3") (pintype "passive"))
    )
    (net (code "38") (name "Net-(Q2-K)") (class "Default")
      (node (ref "C13") (pin "1") (pinfunction "1_1") (pintype "passive"))
      (node (ref "Q2") (pin "1") (pinfunction "K_1") (pintype "passive"))
      (node (ref "Q3") (pin "4") (pinfunction "C_4") (pintype "passive"))
      (node (ref "R11") (pin "2") (pinfunction "2_2") (pintype "passive"))
      (node (ref "R16") (pin "1") (pinfunction "1_1") (pintype "passive"))
    )
    (net (code "39") (name "Net-(Q3-E)") (class "Default")
      (node (ref "F1") (pin "1") (pinfunction "1_1") (pintype "passive"))
      (node (ref "P6") (pin "1") (pinfunction "1_1") (pintype "passive"))
      (node (ref "Q3") (pin "3") (pinfunction "E_3") (pintype "passive"))
    )
    (net (code "40") (name "Net-(Q7-54)") (class "Default")
      (node (ref "L1") (pin "2") (pinfunction "2_2") (pintype "passive"))
      (node (ref "Q7") (pin "2") (pinfunction "54_2") (pintype "passive"))
      (node (ref "TJ5") (pin "1") (pinfunction "1_1") (pintype "passive"))
    )
    (net (code "41") (name "Net-(Q7-B)") (class "Default")
      (node (ref "Q7") (pin "1") (pinfunction "B_1") (pintype "passive"))
      (node (ref "R32") (pin "2") (pinfunction "2_2") (pintype "passive"))
    )
    (net (code "42") (name "Net-(Q7-C)") (class "Default")
      (node (ref "Q7") (pin "3") (pinfunction "C_3") (pintype "passive"))
      (node (ref "R31") (pin "2") (pinfunction "2_2") (pintype "passive"))
      (node (ref "U10") (pin "1") (pinfunction "1A_1") (pintype "input"))
    )
    (net (code "43") (name "Net-(R7-Pad1)") (class "Default")
      (node (ref "R7") (pin "1") (pinfunction "1_1") (pintype "passive"))
      (node (ref "TJ4") (pin "1") (pinfunction "1_1") (pintype "passive"))
    )
    (net (code "44") (name "Net-(U2-RS)") (class "Default")
      (node (ref "R8") (pin "1") (pinfunction "1_1") (pintype "passive"))
      (node (ref "U2") (pin "8") (pinfunction "RS_8") (pintype "power_in"))
    )
    (net (code "45") (name "Net-(U2-VCC)") (class "Default")
      (node (ref "C12") (pin "2") (pinfunction "2_2") (pintype "passive"))
      (node (ref "TJ2") (pin "2") (pinfunction "2_2") (pintype "passive"))
      (node (ref "U2") (pin "3") (pinfunction "VCC_3") (pintype "passive"))
    )
    (net (code "46") (name "Net-(U6-BOOT)") (class "Default")
      (node (ref "C17") (pin "1") (pinfunction "1_1") (pintype "passive"))
      (node (ref "U6") (pin "7") (pinfunction "BOOT_7") (pintype "passive"))
    )
    (net (code "47") (name "Net-(U6-COMP_SEL)") (class "Default")
      (node (ref "R25") (pin "2") (pinfunction "2_2") (pintype "passive"))
      (node (ref "U6") (pin "4") (pinfunction "COMP_SEL_4") (pintype "power_in"))
    )
    (net (code "48") (name "Net-(U6-EN{slash}COMP)") (class "Default")
      (node (ref "R24") (pin "2") (pinfunction "2_2") (pintype "passive"))
      (node (ref "U6") (pin "3") (pinfunction "EN/COMP_3") (pintype "passive"))
    )
    (net (code "49") (name "Net-(U6-LX)") (class "Default")
      (node (ref "C17") (pin "2") (pinfunction "2_2") (pintype "passive"))
      (node (ref "L2") (pin "1") (pinfunction "1_1") (pintype "passive"))
      (node (ref "R23") (pin "2") (pinfunction "2_2") (pintype "passive"))
      (node (ref "U6") (pin "8") (pinfunction "LX_8") (pintype "open_collector"))
    )
    (net (code "50") (name "Net-(U6-SENSE+)") (class "Default")
      (node (ref "C4") (pin "1") (pinfunction "1_1") (pintype "passive"))
      (node (ref "L2") (pin "2") (pinfunction "2_2") (pintype "passive"))
      (node (ref "R22") (pin "1") (pinfunction "1_1") (pintype "passive"))
      (node (ref "U6") (pin "6") (pinfunction "SENSE+_6") (pintype "power_in"))
    )
    (net (code "51") (name "Net-(U6_1-VIN)") (class "Default")
      (node (ref "C10") (pin "1") (pinfunction "1_1") (pintype "passive"))
      (node (ref "C11") (pin "2") (pinfunction "2_2") (pintype "passive"))
      (node (ref "F1") (pin "2") (pinfunction "2_2") (pintype "passive"))
      (node (ref "U6") (pin "1") (pinfunction "VIN_1") (pintype "passive"))
      (node (ref "U6") (pin "2") (pinfunction "VIN_2") (pintype "passive"))
      (node (ref "U6_1") (pin "3") (pinfunction "VIN_3") (pintype "passive"))
    )
    (net (code "52") (name "Net-(U7-PA1)") (class "Default")
      (node (ref "TJ1") (pin "1") (pinfunction "1_1") (pintype "passive"))
      (node (ref "U7") (pin "11") (pinfunction "PA1_11") (pintype "passive"))
    )
    (net (code "53") (name "Net-(U7-PC13)") (class "Default")
      (node (ref "R20") (pin "1") (pinfunction "1_1") (pintype "passive"))
      (node (ref "U7") (pin "2") (pinfunction "PC13_2") (pintype "passive"))
    )
    (net (code "54") (name "Net-(U7-PC14-OSC32_IN)") (class "Default")
      (node (ref "C21") (pin "1") (pinfunction "1_1") (pintype "passive"))
      (node (ref "U7") (pin "3") (pinfunction "PC14-OSC32_IN_3") (pintype "passive"))
      (node (ref "Y1") (pin "1") (pinfunction "OSC1_1") (pintype "passive"))
    )
    (net (code "55") (name "Net-(U7-PC15-OSC32_OUT)") (class "Default")
      (node (ref "C22") (pin "1") (pinfunction "1_1") (pintype "passive"))
      (node (ref "U7") (pin "4") (pinfunction "PC15-OSC32_OUT_4") (pintype "passive"))
      (node (ref "Y1") (pin "2") (pinfunction "OSC2_2") (pintype "passive"))
    )
    (net (code "56") (name "Net-(U9A-IN-)") (class "Default")
      (node (ref "R33") (pin "1") (pinfunction "1_1") (pintype "passive"))
      (node (ref "U9") (pin "1") (pinfunction "OUT_1") (pintype "output"))
      (node (ref "U9") (pin "2") (pinfunction "IN-_2") (pintype "input"))
    )
    (net (code "57") (name "Net-(U9B-IN+)") (class "Default")
      (node (ref "R13") (pin "2") (pinfunction "2_2") (pintype "passive"))
      (node (ref "R33") (pin "2") (pinfunction "2_2") (pintype "passive"))
      (node (ref "U9") (pin "5") (pinfunction "IN+_5") (pintype "input"))
    )
    (net (code "58") (name "Net-(U9B-IN-)") (class "Default")
      (node (ref "R10") (pin "1") (pinfunction "1_1") (pintype "passive"))
      (node (ref "R12") (pin "1") (pinfunction "1_1") (pintype "passive"))
      (node (ref "U9") (pin "6") (pinfunction "IN-_6") (pintype "input"))
    )
    (net (code "59") (name "unconnected-(U2-Vref-Pad5)") (class "Default")
      (node (ref "U2") (pin "5") (pinfunction "Vref_5") (pintype "passive+no_connect"))
    )
    (net (code "60") (name "unconnected-(U3-VOUT-Pad4)") (class "Default")
      (node (ref "U3") (pin "4") (pinfunction "VOUT_4") (pintype "passive+no_connect"))
    )
    (net (code "61") (name "unconnected-(U6_1-VOUT-Pad4)") (class "Default")
      (node (ref "U6_1") (pin "4") (pinfunction "VOUT_4") (pintype "passive+no_connect"))
    )
    (net (code "62") (name "unconnected-(U7-PA0-Pad10)") (class "Default")
      (node (ref "U7") (pin "10") (pinfunction "PA0_10") (pintype "power_in+no_connect"))
    )
    (net (code "63") (name "unconnected-(U7-PA4-Pad14)") (class "Default")
      (node (ref "U7") (pin "14") (pinfunction "PA4_14") (pintype "passive+no_connect"))
    )
    (net (code "64") (name "unconnected-(U7-PA8-Pad29)") (class "Default")
      (node (ref "U7") (pin "29") (pinfunction "PA8_29") (pintype "passive+no_connect"))
    )
    (net (code "65") (name "unconnected-(U7-PA15-Pad38)") (class "Default")
      (node (ref "U7") (pin "38") (pinfunction "PA15_38") (pintype "passive+no_connect"))
    )
    (net (code "66") (name "unconnected-(U7-PB2-Pad20)") (class "Default")
      (node (ref "U7") (pin "20") (pinfunction "PB2_20") (pintype "passive+no_connect"))
    )
    (net (code "67") (name "unconnected-(U7-PB3-Pad39)") (class "Default")
      (node (ref "U7") (pin "39") (pinfunction "PB3_39") (pintype "passive+no_connect"))
    )
    (net (code "68") (name "unconnected-(U7-PB4-Pad40)") (class "Default")
      (node (ref "U7") (pin "40") (pinfunction "PB4_40") (pintype "passive+no_connect"))
    )
    (net (code "69") (name "unconnected-(U7-PB5-Pad41)") (class "Default")
      (node (ref "U7") (pin "41") (pinfunction "PB5_41") (pintype "passive"))
    )
    (net (code "70") (name "unconnected-(U7-PB6-Pad42)") (class "Default")
      (node (ref "U7") (pin "42") (pinfunction "PB6_42") (pintype "passive"))
    )
    (net (code "71") (name "unconnected-(U7-PB7-Pad43)") (class "Default")
      (node (ref "U7") (pin "43") (pinfunction "PB7_43") (pintype "passive+no_connect"))
    )
    (net (code "72") (name "unconnected-(U7-PB13-Pad26)") (class "Default")
      (node (ref "U7") (pin "26") (pinfunction "PB13_26") (pintype "passive+no_connect"))
    )
    (net (code "73") (name "unconnected-(U7-PB14-Pad27)") (class "Default")
      (node (ref "U7") (pin "27") (pinfunction "PB14_27") (pintype "passive+no_connect"))
    )
    (net (code "74") (name "unconnected-(U7-PB15-Pad28)") (class "Default")
      (node (ref "U7") (pin "28") (pinfunction "PB15_28") (pintype "passive+no_connect"))
    )
    (net (code "75") (name "unconnected-(U7-PF0-OSC_IN-Pad5)") (class "Default")
      (node (ref "U7") (pin "5") (pinfunction "PF0-OSC_IN_5") (pintype "passive+no_connect"))
    )
    (net (code "76") (name "unconnected-(U7-PF1-OSC_OUT-Pad6)") (class "Default")
      (node (ref "U7") (pin "6") (pinfunction "PF1-OSC_OUT_6") (pintype "passive+no_connect"))
    )
    (net (code "77") (name "unconnected-(U10-2A-Pad3)") (class "Default")
      (node (ref "U10") (pin "3") (pinfunction "2A_3") (pintype "input+no_connect"))
    )
    (net (code "78") (name "unconnected-(U10-2Y-Pad4)") (class "Default")
      (node (ref "U10") (pin "4") (pinfunction "2Y_4") (pintype "output+no_connect"))
    )
    (net (code "79") (name "unconnected-(U10-3A-Pad5)") (class "Default")
      (node (ref "U10") (pin "5") (pinfunction "3A_5") (pintype "input+no_connect"))
    )
    (net (code "80") (name "unconnected-(U10-3Y-Pad6)") (class "Default")
      (node (ref "U10") (pin "6") (pinfunction "3Y_6") (pintype "output+no_connect"))
    )
    (net (code "81") (name "unconnected-(U10-4A-Pad9)") (class "Default")
      (node (ref "U10") (pin "9") (pinfunction "4A_9") (pintype "input+no_connect"))
    )
    (net (code "82") (name "unconnected-(U10-4Y-Pad8)") (class "Default")
      (node (ref "U10") (pin "8") (pinfunction "4Y_8") (pintype "output+no_connect"))
    )
    (net (code "83") (name "unconnected-(U10-5A-Pad11)") (class "Default")
      (node (ref "U10") (pin "11") (pinfunction "5A_11") (pintype "input+no_connect"))
    )
    (net (code "84") (name "unconnected-(U10-5Y-Pad10)") (class "Default")
      (node (ref "U10") (pin "10") (pinfunction "5Y_10") (pintype "output+no_connect"))
    )
    (net (code "85") (name "unconnected-(U10-6A-Pad13)") (class "Default")
      (node (ref "U10") (pin "13") (pinfunction "6A_13") (pintype "input+no_connect"))
    )
    (net (code "86") (name "unconnected-(U10-6Y-Pad12)") (class "Default")
      (node (ref "U10") (pin "12") (pinfunction "6Y_12") (pintype "output+no_connect"))
    )
  )
)
